# board_v3.net
KiCad netlist of a schematic drawn in EAGLE
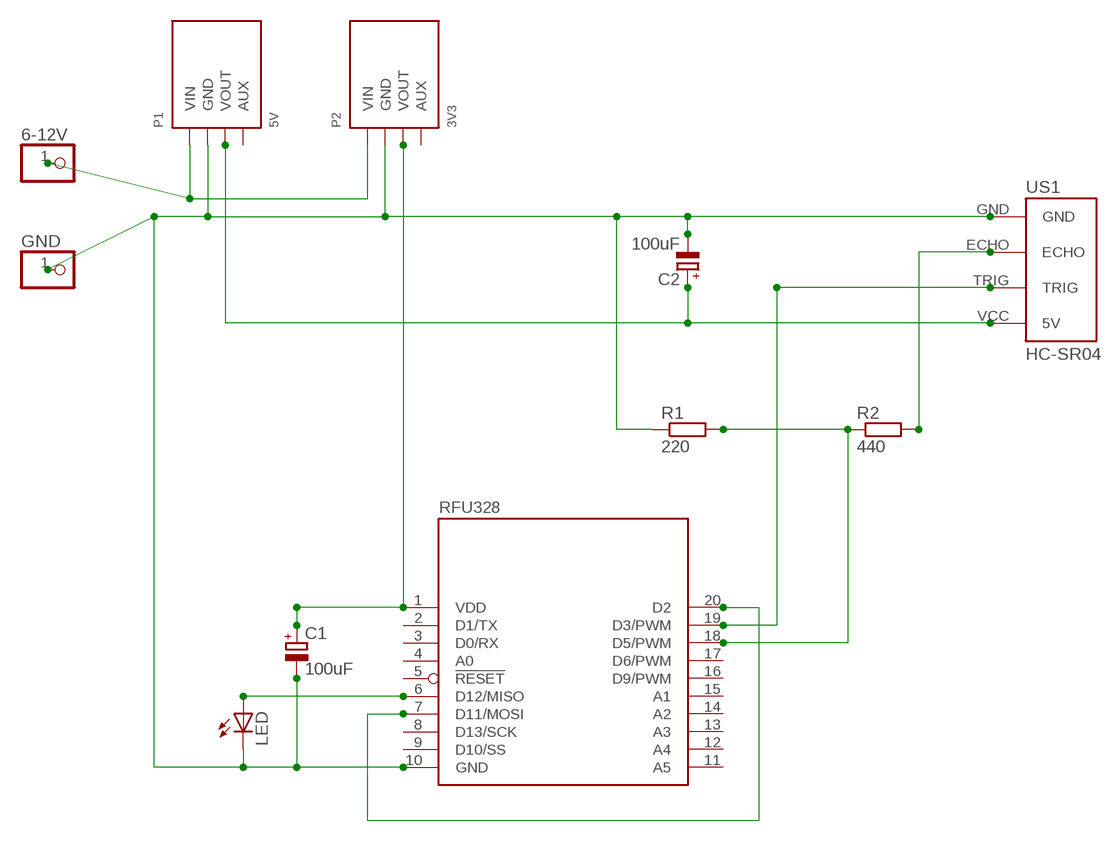
[diagram p0: schematic, sheet 1]

(export (version "E")
  (design (tool "Eeschema 10.0.6"))
  (components
    (comp (ref "6-12V")
      (value "PINHD-1X1")
      (footprint "eagle-import:1X01")
      (libsource (lib "eagle-import") (part "PINHD-1X1"))
    )
    (comp (ref "C1")
      (value "100uF")
      (footprint "eagle-import:E5-5")
      (libsource (lib "eagle-import") (part "CPOL-EUE5-5"))
    )
    (comp (ref "C2")
      (value "100uF")
      (footprint "eagle-import:E5-5")
      (libsource (lib "eagle-import") (part "CPOL-EUE5-5"))
    )
    (comp (ref "GND")
      (value "PINHD-1X1")
      (footprint "eagle-import:1X01")
      (libsource (lib "eagle-import") (part "PINHD-1X1"))
    )
    (comp (ref "LED")
      (value "TLLR4400")
      (footprint "eagle-import:LED3MM")
      (fields (field (name "MF") "VISHAY SEMICONDUCTOR"))
      (libsource (lib "eagle-import") (part "TLLR4400"))
    )
    (comp (ref "P1")
      (value "5V")
      (footprint "eagle-import:POWER-POD-REF")
      (libsource (lib "eagle-import") (part "POWER-POD-REFRENCE"))
    )
    (comp (ref "P2")
      (value "3V3")
      (footprint "eagle-import:POWER-POD-REF")
      (libsource (lib "eagle-import") (part "POWER-POD-REFRENCE"))
    )
    (comp (ref "R1")
      (value "220")
      (footprint "eagle-import:0207_7")
      (libsource (lib "eagle-import") (part "R-EU_0207/7"))
    )
    (comp (ref "R2")
      (value "440")
      (footprint "eagle-import:0207_7")
      (libsource (lib "eagle-import") (part "R-EU_0207/7"))
    )
    (comp (ref "RFU328")
      (value "RFµ-328-SOCKET-V2.0")
      (footprint "eagle-import:RFµ-SOCKET-V2.0")
      (libsource (lib "eagle-import") (part "RFµ-328-SOCKET-V2.0"))
    )
    (comp (ref "US1")
      (value "HC-SR04")
      (footprint "eagle-import:HC-SR04_FOOTPRINT")
      (libsource (lib "eagle-import") (part "HC-SR04"))
    )
  )
  (nets
    (net (code "1") (name "Net-(LED-C)") (class "Default")
      (node (ref "C1") (pin "-") (pinfunction "-_-") (pintype "passive"))
      (node (ref "C2") (pin "-") (pinfunction "-_-") (pintype "passive"))
      (node (ref "GND") (pin "1") (pinfunction "1_1") (pintype "passive"))
      (node (ref "LED") (pin "K") (pinfunction "C_K") (pintype "passive"))
      (node (ref "P1") (pin "2") (pinfunction "GND_2") (pintype "bidirectional"))
      (node (ref "P2") (pin "2") (pinfunction "GND_2") (pintype "bidirectional"))
      (node (ref "R1") (pin "1") (pinfunction "1_1") (pintype "passive"))
      (node (ref "RFU328") (pin "10") (pinfunction "GND_10") (pintype "power_in"))
      (node (ref "US1") (pin "GND") (pinfunction "GND_GND") (pintype "bidirectional"))
    )
    (net (code "2") (name "Net-(P1-VIN)") (class "Default")
      (node (ref "6-12V") (pin "1") (pinfunction "1_1") (pintype "passive"))
      (node (ref "P1") (pin "1") (pinfunction "VIN_1") (pintype "bidirectional"))
      (node (ref "P2") (pin "1") (pinfunction "VIN_1") (pintype "bidirectional"))
    )
    (net (code "3") (name "Net-(P1-VOUT)") (class "Default")
      (node (ref "C2") (pin "+") (pinfunction "+_+") (pintype "passive"))
      (node (ref "P1") (pin "3") (pinfunction "VOUT_3") (pintype "bidirectional"))
      (node (ref "US1") (pin "VCC") (pinfunction "5V_VCC") (pintype "bidirectional"))
    )
    (net (code "4") (name "Net-(P2-VOUT)") (class "Default")
      (node (ref "C1") (pin "+") (pinfunction "+_+") (pintype "passive"))
      (node (ref "P2") (pin "3") (pinfunction "VOUT_3") (pintype "bidirectional"))
      (node (ref "RFU328") (pin "1") (pinfunction "VDD_1") (pintype "power_in"))
    )
    (net (code "5") (name "Net-(R2-Pad2)") (class "Default")
      (node (ref "R2") (pin "2") (pinfunction "2_2") (pintype "passive"))
      (node (ref "US1") (pin "ECHO") (pinfunction "ECHO_ECHO") (pintype "bidirectional"))
    )
    (net (code "6") (name "Net-(RFU328-D3{slash}PWM)") (class "Default")
      (node (ref "RFU328") (pin "19") (pinfunction "D3/PWM_19") (pintype "bidirectional"))
      (node (ref "US1") (pin "TRIG") (pinfunction "TRIG_TRIG") (pintype "bidirectional"))
    )
    (net (code "7") (name "Net-(RFU328-D5{slash}PWM)") (class "Default")
      (node (ref "R1") (pin "2") (pinfunction "2_2") (pintype "passive"))
      (node (ref "R2") (pin "1") (pinfunction "1_1") (pintype "passive"))
      (node (ref "RFU328") (pin "18") (pinfunction "D5/PWM_18") (pintype "bidirectional"))
    )
    (net (code "8") (name "Net-(RFU328-D11{slash}MOSI)") (class "Default")
      (node (ref "RFU328") (pin "20") (pinfunction "D2_20") (pintype "bidirectional"))
      (node (ref "RFU328") (pin "7") (pinfunction "D11/MOSI_7") (pintype "bidirectional"))
    )
    (net (code "9") (name "Net-(RFU328-D12{slash}MISO)") (class "Default")
      (node (ref "LED") (pin "A") (pinfunction "A_A") (pintype "passive"))
      (node (ref "RFU328") (pin "6") (pinfunction "D12/MISO_6") (pintype "bidirectional"))
    )
    (net (code "10") (name "unconnected-(P1-AUX-Pad4)") (class "Default")
      (node (ref "P1") (pin "4") (pinfunction "AUX_4") (pintype "bidirectional"))
    )
    (net (code "11") (name "unconnected-(P2-AUX-Pad4)") (class "Default")
      (node (ref "P2") (pin "4") (pinfunction "AUX_4") (pintype "bidirectional"))
    )
    (net (code "12") (name "unconnected-(RFU328-A0-Pad4)") (class "Default")
      (node (ref "RFU328") (pin "4") (pinfunction "A0_4") (pintype "bidirectional"))
    )
    (net (code "13") (name "unconnected-(RFU328-A1-Pad15)") (class "Default")
      (node (ref "RFU328") (pin "15") (pinfunction "A1_15") (pintype "bidirectional"))
    )
    (net (code "14") (name "unconnected-(RFU328-A2-Pad14)") (class "Default")
      (node (ref "RFU328") (pin "14") (pinfunction "A2_14") (pintype "bidirectional"))
    )
    (net (code "15") (name "unconnected-(RFU328-A3-Pad13)") (class "Default")
      (node (ref "RFU328") (pin "13") (pinfunction "A3_13") (pintype "bidirectional"))
    )
    (net (code "16") (name "unconnected-(RFU328-A4-Pad12)") (class "Default")
      (node (ref "RFU328") (pin "12") (pinfunction "A4_12") (pintype "output"))
    )
    (net (code "17") (name "unconnected-(RFU328-A5-Pad11)") (class "Default")
      (node (ref "RFU328") (pin "11") (pinfunction "A5_11") (pintype "bidirectional"))
    )
    (net (code "18") (name "unconnected-(RFU328-D0{slash}RX-Pad3)") (class "Default")
      (node (ref "RFU328") (pin "3") (pinfunction "D0/RX_3") (pintype "input"))
    )
    (net (code "19") (name "unconnected-(RFU328-D1{slash}TX-Pad2)") (class "Default")
      (node (ref "RFU328") (pin "2") (pinfunction "D1/TX_2") (pintype "output"))
    )
    (net (code "20") (name "unconnected-(RFU328-D6{slash}PWM-Pad17)") (class "Default")
      (node (ref "RFU328") (pin "17") (pinfunction "D6/PWM_17") (pintype "bidirectional"))
    )
    (net (code "21") (name "unconnected-(RFU328-D9{slash}PWM-Pad16)") (class "Default")
      (node (ref "RFU328") (pin "16") (pinfunction "D9/PWM_16") (pintype "input"))
    )
    (net (code "22") (name "unconnected-(RFU328-D10{slash}SS-Pad9)") (class "Default")
      (node (ref "RFU328") (pin "9") (pinfunction "D10/SS_9") (pintype "bidirectional"))
    )
    (net (code "23") (name "unconnected-(RFU328-D13{slash}SCK-Pad8)") (class "Default")
      (node (ref "RFU328") (pin "8") (pinfunction "D13/SCK_8") (pintype "bidirectional"))
    )
    (net (code "24") (name "unconnected-(RFU328-~{RESET}-Pad5)") (class "Default")
      (node (ref "RFU328") (pin "5") (pinfunction "~{RESET}_5") (pintype "input"))
    )
  )
)
